# Frame2TTL.net
KiCad netlist of a schematic drawn in EAGLE
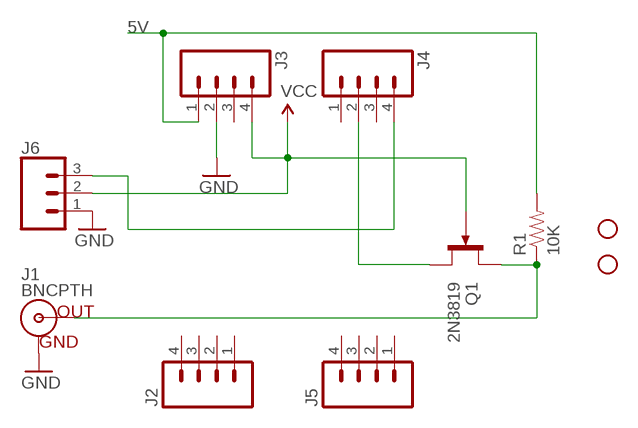
[diagram p0: schematic, sheet 1]

(export (version "E")
  (design (tool "Eeschema 10.0.6"))
  (components
    (comp (ref "H1")
      (value "STAND-OFFTIGHT")
      (footprint "eagle-import:STAND-OFF-TIGHT")
      (libsource (lib "eagle-import") (part "STAND-OFFTIGHT"))
    )
    (comp (ref "H2")
      (value "STAND-OFFTIGHT")
      (footprint "eagle-import:STAND-OFF-TIGHT")
      (libsource (lib "eagle-import") (part "STAND-OFFTIGHT"))
    )
    (comp (ref "J1")
      (value "BNCPTH")
      (footprint "eagle-import:BNC")
      (libsource (lib "eagle-import") (part "BNCPTH"))
    )
    (comp (ref "J2")
      (value "M04PTH")
      (footprint "eagle-import:1X04")
      (libsource (lib "eagle-import") (part "M04PTH"))
    )
    (comp (ref "J3")
      (value "M04PTH")
      (footprint "eagle-import:1X04")
      (libsource (lib "eagle-import") (part "M04PTH"))
    )
    (comp (ref "J4")
      (value "M04PTH")
      (footprint "eagle-import:1X04")
      (libsource (lib "eagle-import") (part "M04PTH"))
    )
    (comp (ref "J5")
      (value "M04PTH")
      (footprint "eagle-import:1X04")
      (libsource (lib "eagle-import") (part "M04PTH"))
    )
    (comp (ref "J6")
      (value "CONN_03SCREW_LOCK")
      (footprint "eagle-import:SCREWTERMINAL-3.5MM-3_LOCK.007S")
      (libsource (lib "eagle-import") (part "CONN_03SCREW_LOCK"))
    )
    (comp (ref "Q1")
      (value "2N3819")
      (footprint "eagle-import:TO92F")
      (libsource (lib "eagle-import") (part "2N3819"))
    )
    (comp (ref "R1")
      (value "10K")
      (footprint "eagle-import:AXIAL-0.3")
      (libsource (lib "eagle-import") (part "RESISTORAXIAL-0.3"))
    )
  )
  (nets
    (net (code "1") (name "GND") (class "Default")
      (node (ref "J1") (pin "GND") (pinfunction "GND_GND") (pintype "bidirectional"))
      (node (ref "J3") (pin "2") (pinfunction "2_2") (pintype "passive"))
      (node (ref "J6") (pin "1") (pinfunction "1_1") (pintype "passive"))
    )
    (net (code "2") (name "Net-(J1-OUT)") (class "Default")
      (node (ref "J1") (pin "S") (pinfunction "OUT_S") (pintype "bidirectional"))
      (node (ref "Q1") (pin "D") (pinfunction "D_D") (pintype "passive"))
      (node (ref "R1") (pin "P$1") (pinfunction "1_P$1") (pintype "passive"))
    )
    (net (code "3") (name "Net-(J4-Pad2)") (class "Default")
      (node (ref "J4") (pin "2") (pinfunction "2_2") (pintype "passive"))
      (node (ref "Q1") (pin "S") (pinfunction "S_S") (pintype "passive"))
    )
    (net (code "4") (name "Net-(J4-Pad4)") (class "Default")
      (node (ref "J4") (pin "4") (pinfunction "4_4") (pintype "passive"))
      (node (ref "J6") (pin "3") (pinfunction "3_3") (pintype "passive"))
    )
    (net (code "5") (name "Net-(R1-2)") (class "Default")
      (node (ref "J3") (pin "1") (pinfunction "1_1") (pintype "passive"))
      (node (ref "R1") (pin "P$2") (pinfunction "2_P$2") (pintype "passive"))
    )
    (net (code "6") (name "VCC") (class "Default")
      (node (ref "J3") (pin "4") (pinfunction "4_4") (pintype "passive"))
      (node (ref "J6") (pin "2") (pinfunction "2_2") (pintype "passive"))
      (node (ref "Q1") (pin "G") (pinfunction "G_G") (pintype "passive"))
    )
    (net (code "7") (name "unconnected-(J2-Pad1)") (class "Default")
      (node (ref "J2") (pin "1") (pinfunction "1_1") (pintype "passive"))
    )
    (net (code "8") (name "unconnected-(J2-Pad2)") (class "Default")
      (node (ref "J2") (pin "2") (pinfunction "2_2") (pintype "passive"))
    )
    (net (code "9") (name "unconnected-(J2-Pad3)") (class "Default")
      (node (ref "J2") (pin "3") (pinfunction "3_3") (pintype "passive"))
    )
    (net (code "10") (name "unconnected-(J2-Pad4)") (class "Default")
      (node (ref "J2") (pin "4") (pinfunction "4_4") (pintype "passive"))
    )
    (net (code "11") (name "unconnected-(J3-Pad3)") (class "Default")
      (node (ref "J3") (pin "3") (pinfunction "3_3") (pintype "passive"))
    )
    (net (code "12") (name "unconnected-(J4-Pad1)") (class "Default")
      (node (ref "J4") (pin "1") (pinfunction "1_1") (pintype "passive"))
    )
    (net (code "13") (name "unconnected-(J4-Pad3)") (class "Default")
      (node (ref "J4") (pin "3") (pinfunction "3_3") (pintype "passive"))
    )
    (net (code "14") (name "unconnected-(J5-Pad1)") (class "Default")
      (node (ref "J5") (pin "1") (pinfunction "1_1") (pintype "passive"))
    )
    (net (code "15") (name "unconnected-(J5-Pad2)") (class "Default")
      (node (ref "J5") (pin "2") (pinfunction "2_2") (pintype "passive"))
    )
    (net (code "16") (name "unconnected-(J5-Pad3)") (class "Default")
      (node (ref "J5") (pin "3") (pinfunction "3_3") (pintype "passive"))
    )
    (net (code "17") (name "unconnected-(J5-Pad4)") (class "Default")
      (node (ref "J5") (pin "4") (pinfunction "4_4") (pintype "passive"))
    )
  )
)
